# BW1098OAK_Power_Supply.net
KiCad netlist of a schematic drawn in Altium Designer
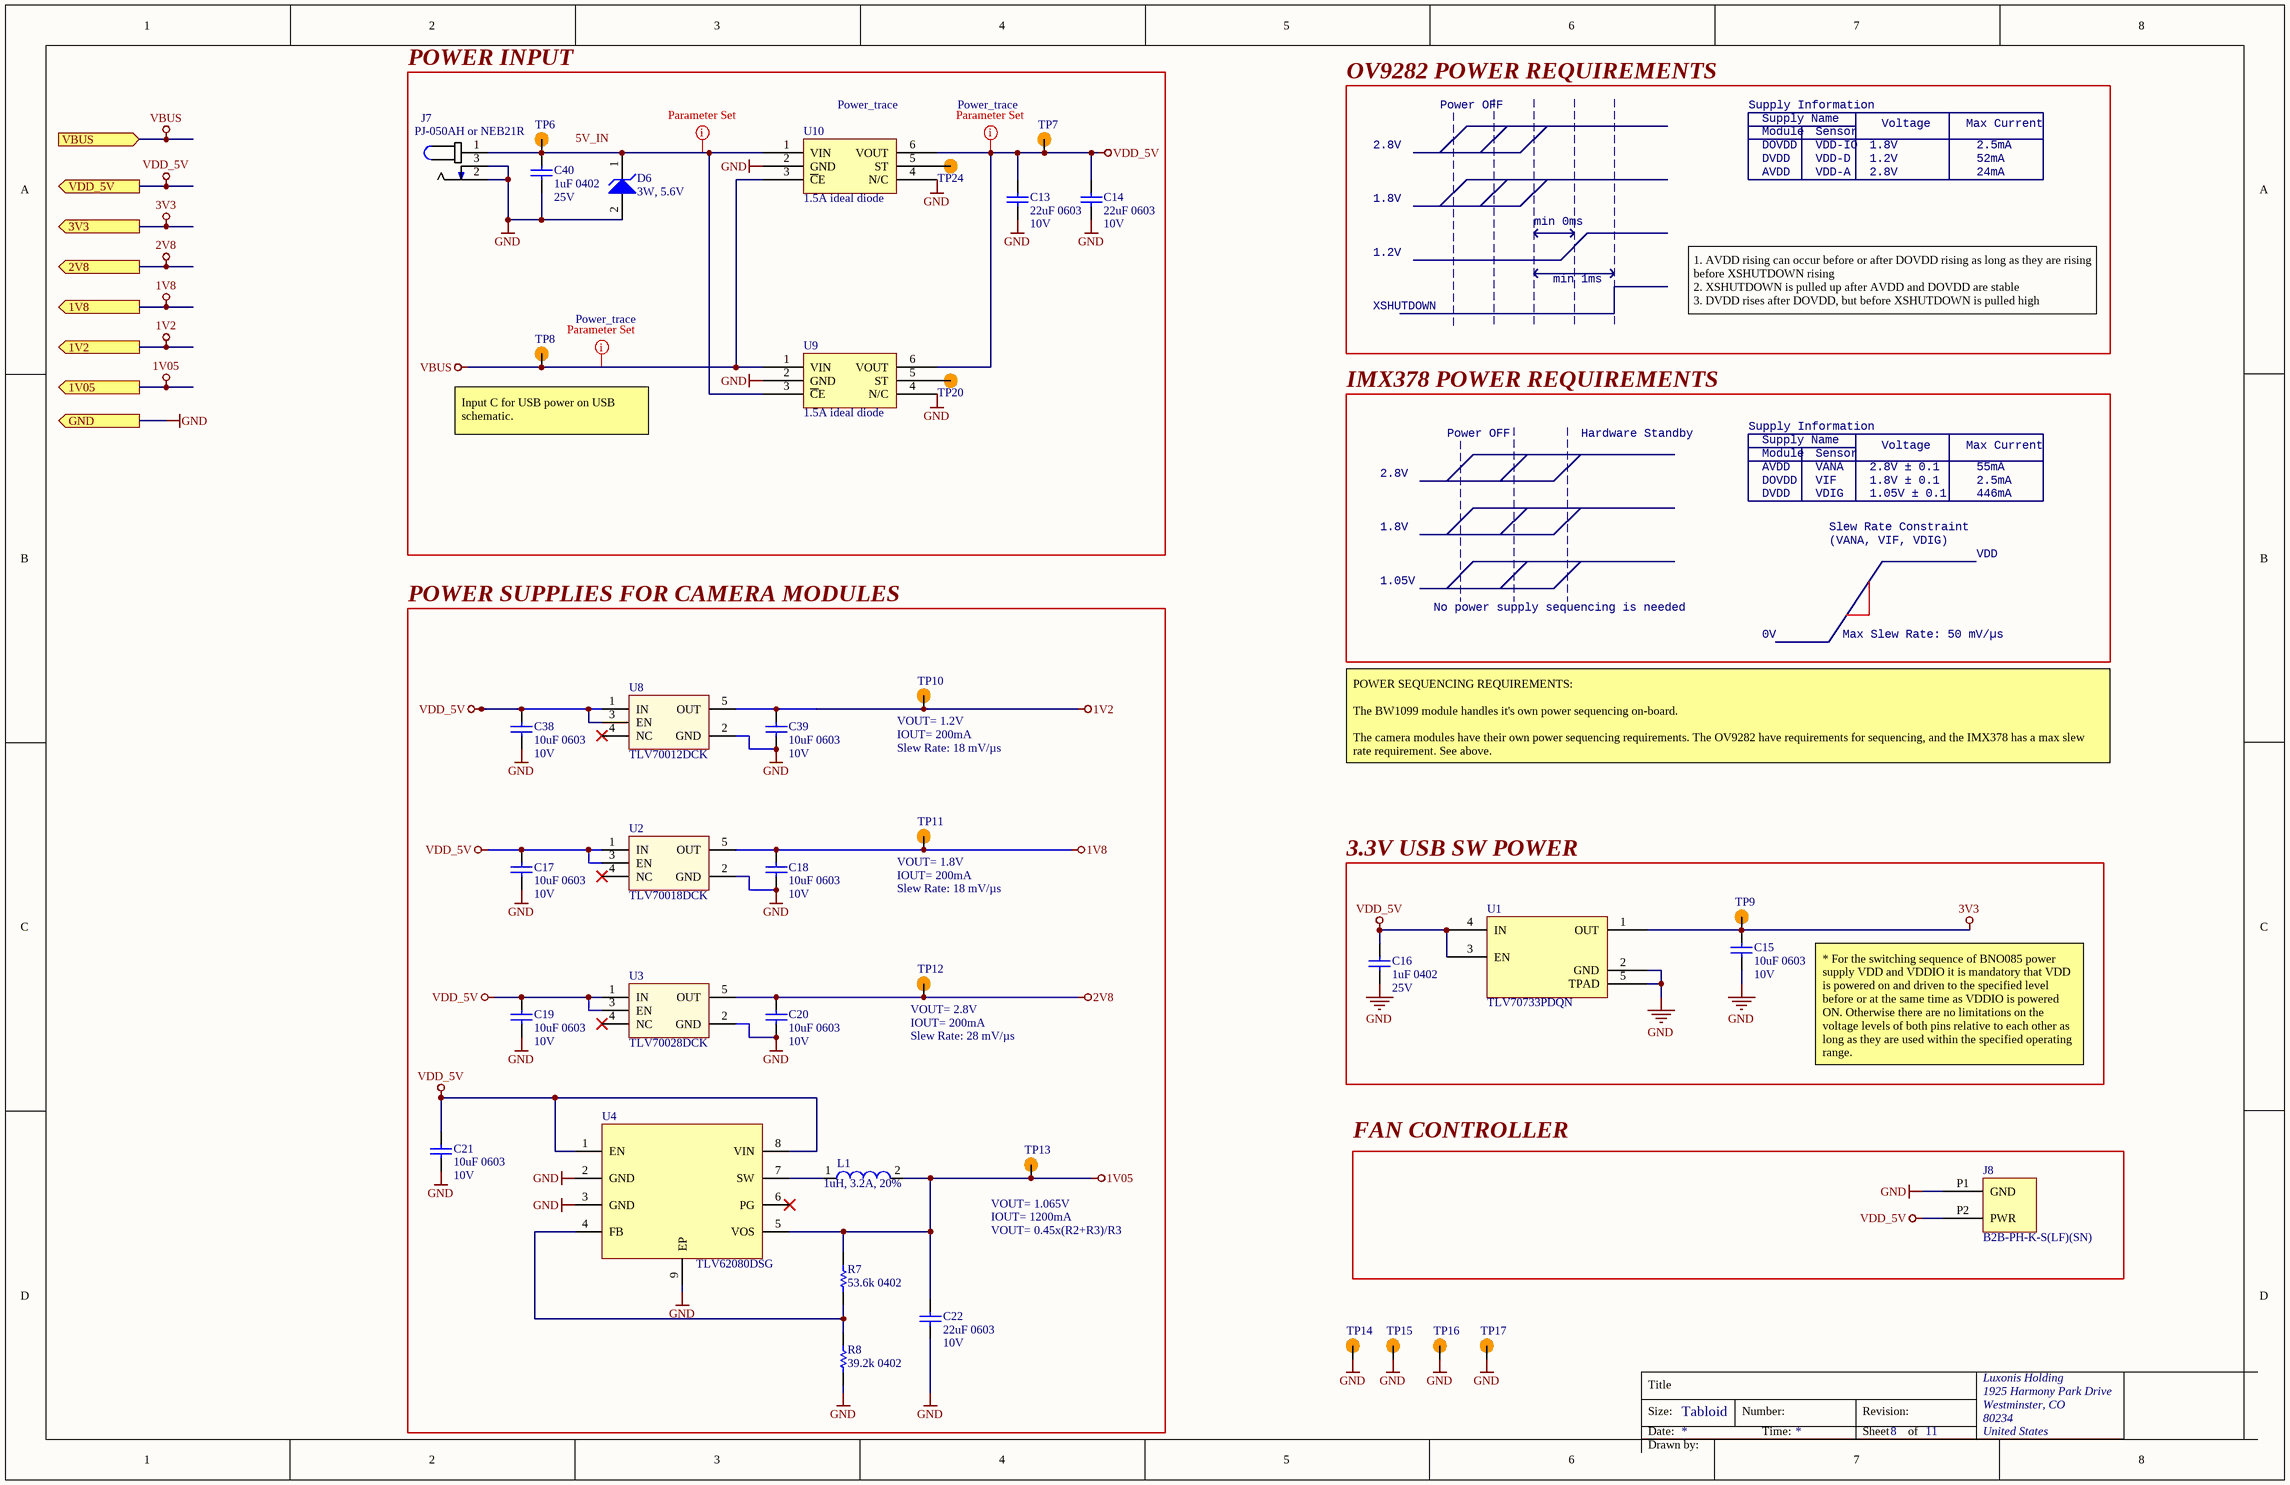
[diagram p0: BW1098OAK_Power_Supply.SchDoc]

(export (version "E")
  (design (tool "Eeschema 10.0.6"))
  (components
    (comp (ref "C13")
      (value "22uF 0603")
      (footprint "CAP_Altium_Vault_Generic:CAPC0603(1608)100_L")
      (description "CAP CER 22UF 10V X5R 0603 20%")
      (fields (field (name "TOLERANCE") "20%") (field (name "VOLTAGE RATING") "10V"))
      (libsource (lib "LuxonisMaster") (part "GRM188R61A226ME15D"))
    )
    (comp (ref "C14")
      (value "22uF 0603")
      (footprint "CAP_Altium_Vault_Generic:CAPC0603(1608)100_L")
      (description "CAP CER 22UF 10V X5R 0603 20%")
      (fields (field (name "TOLERANCE") "20%") (field (name "VOLTAGE RATING") "10V"))
      (libsource (lib "LuxonisMaster") (part "GRM188R61A226ME15D"))
    )
    (comp (ref "C15")
      (value "10uF 0603")
      (footprint "CAP_Altium_Vault_Generic:CAPC0603(1608)100_L")
      (description "CAP CER 10UF 10V X5R 0603 20%")
      (fields (field (name "TOLERANCE") "20%") (field (name "VOLTAGE RATING") "10V"))
      (libsource (lib "LuxonisMaster") (part "GRM188R61A106ME69D"))
    )
    (comp (ref "C16")
      (value "1uF 0402")
      (footprint "CAP_Altium_Vault_Generic:CAPC0402(1005)70_L")
      (description "CAP CER 1UF 25V X5R 0402 10%")
      (fields
        (field (name "TOLERANCE") "10%")
        (field (name "VOLTAGE") "25V")
        (field (name "VOLTAGE RATING") "25V")
      )
      (libsource (lib "LuxonisMaster") (part "GRM155R61E105KA12D"))
    )
    (comp (ref "C17")
      (value "10uF 0603")
      (footprint "CAP_Altium_Vault_Generic:CAPC0603(1608)100_L")
      (description "CAP CER 10UF 10V X5R 0603 20%")
      (fields (field (name "TOLERANCE") "20%") (field (name "VOLTAGE RATING") "10V"))
      (libsource (lib "LuxonisMaster") (part "GRM188R61A106ME69D"))
    )
    (comp (ref "C18")
      (value "10uF 0603")
      (footprint "CAP_Altium_Vault_Generic:CAPC0603(1608)100_L")
      (description "CAP CER 10UF 10V X5R 0603 20%")
      (fields (field (name "TOLERANCE") "20%") (field (name "VOLTAGE RATING") "10V"))
      (libsource (lib "LuxonisMaster") (part "GRM188R61A106ME69D"))
    )
    (comp (ref "C19")
      (value "10uF 0603")
      (footprint "CAP_Altium_Vault_Generic:CAPC0603(1608)100_L")
      (description "CAP CER 10UF 10V X5R 0603 20%")
      (fields (field (name "TOLERANCE") "20%") (field (name "VOLTAGE RATING") "10V"))
      (libsource (lib "LuxonisMaster") (part "GRM188R61A106ME69D"))
    )
    (comp (ref "C20")
      (value "10uF 0603")
      (footprint "CAP_Altium_Vault_Generic:CAPC0603(1608)100_L")
      (description "CAP CER 10UF 10V X5R 0603 20%")
      (fields (field (name "TOLERANCE") "20%") (field (name "VOLTAGE RATING") "10V"))
      (libsource (lib "LuxonisMaster") (part "GRM188R61A106ME69D"))
    )
    (comp (ref "C21")
      (value "10uF 0603")
      (footprint "CAP_Altium_Vault_Generic:CAPC0603(1608)100_L")
      (description "CAP CER 10UF 10V X5R 0603 20%")
      (fields (field (name "TOLERANCE") "20%") (field (name "VOLTAGE RATING") "10V"))
      (libsource (lib "LuxonisMaster") (part "GRM188R61A106ME69D"))
    )
    (comp (ref "C22")
      (value "22uF 0603")
      (footprint "CAP_Altium_Vault_Generic:CAPC0603(1608)100_L")
      (description "CAP CER 22UF 10V X5R 0603 20%")
      (fields (field (name "TOLERANCE") "20%") (field (name "VOLTAGE RATING") "10V"))
      (libsource (lib "LuxonisMaster") (part "GRM188R61A226ME15D"))
    )
    (comp (ref "C38")
      (value "10uF 0603")
      (footprint "CAP_Altium_Vault_Generic:CAPC0603(1608)100_L")
      (description "CAP CER 10UF 10V X5R 0603 20%")
      (fields (field (name "TOLERANCE") "20%") (field (name "VOLTAGE RATING") "10V"))
      (libsource (lib "LuxonisMaster") (part "GRM188R61A106ME69D"))
    )
    (comp (ref "C39")
      (value "10uF 0603")
      (footprint "CAP_Altium_Vault_Generic:CAPC0603(1608)100_L")
      (description "CAP CER 10UF 10V X5R 0603 20%")
      (fields (field (name "TOLERANCE") "20%") (field (name "VOLTAGE RATING") "10V"))
      (libsource (lib "LuxonisMaster") (part "GRM188R61A106ME69D"))
    )
    (comp (ref "C40")
      (value "1uF 0402")
      (footprint "CAP_Altium_Vault_Generic:CAPC0402(1005)70_L")
      (description "CAP CER 1UF 25V X5R 0402 10%")
      (fields
        (field (name "TOLERANCE") "10%")
        (field (name "VOLTAGE") "25V")
        (field (name "VOLTAGE RATING") "25V")
      )
      (libsource (lib "LuxonisMaster") (part "GRM155R61E105KA12D"))
    )
    (comp (ref "D6")
      (value "3W, 5.6V")
      (footprint "BW1098OBC_R3M1E3:1SMB5919BT3G")
      (description "DIODE ZENER 5.6V 3W SMB")
      (fields (field (name "TOLERANCE") "5%"))
      (libsource (lib "BW1098OAK_R0M0E0") (part "1SMB5919BT3G"))
    )
    (comp (ref "J7")
      (value "PJ-050AH or NEB21R")
      (footprint "LuxonisMaster:PJ-050AH/NEB21R_COMBO")
      (description "CONN POWER PIN 2 POS RA PTH Barrel jack 2.1mm x 5.5mm combo footprint")
      (libsource (lib "LuxonisMaster") (part "PJ-050AH/NEB21R_COMBO"))
    )
    (comp (ref "J8")
      (value "B2B-PH-K-S(LF)(SN)")
      (footprint "LuxonisMaster:B2B-PH-K-S(LF)(SN)")
      (description "CONN HEADER VERT 2POS 2MM")
      (libsource (lib "LuxonisMaster") (part "B2B-PH-K-S(LF)(SN)"))
    )
    (comp (ref "L1")
      (value "1uH, 3.2A, 20%")
      (footprint "LuxonisMaster:DFE252012P-1R0M=P2")
      (description "FIXED IND 1UH 3.2A 42 MOHM SMD")
      (fields
        (field (name "MANUFACTURER") "Murata")
        (field (name "MANUFACTURER PART NUMBER") "DFE252012P-1R0M=P2")
      )
      (libsource (lib "LuxonisMaster") (part "DFE252012P-1R0M=P2"))
    )
    (comp (ref "R7")
      (value "53.6k 0402")
      (footprint "RES_Altium_Vault_Generic:RESC0402(1005)_L")
      (description "RES SMD 53.6K OHM 1% 1/16W 0402")
      (fields (field (name "TOLERANCE") "1%"))
      (libsource (lib "LuxonisMaster") (part "CRCW040253K6FKED"))
    )
    (comp (ref "R8")
      (value "39.2k 0402")
      (footprint "RES_Altium_Vault_Generic:RESC0402(1005)_L")
      (description "RES SMD 39.2K OHM 1% 1/16W 0402")
      (fields (field (name "TOLERANCE") "1%"))
      (libsource (lib "LuxonisMaster") (part "CRCW040239K2FKED"))
    )
    (comp (ref "TP6")
      (value "TP100_200_NS")
      (footprint "LuxonisMaster:TP100_200_NS")
      (libsource (lib "LuxonisMaster") (part "TEST_POINT"))
    )
    (comp (ref "TP7")
      (value "TP100_200_NS")
      (footprint "LuxonisMaster:TP100_200_NS")
      (libsource (lib "LuxonisMaster") (part "TEST_POINT"))
    )
    (comp (ref "TP8")
      (value "TP100_200_NS")
      (footprint "LuxonisMaster:TP100_200_NS")
      (libsource (lib "LuxonisMaster") (part "TEST_POINT"))
    )
    (comp (ref "TP9")
      (value "TP100_200_NS")
      (footprint "LuxonisMaster:TP100_200_NS")
      (libsource (lib "LuxonisMaster") (part "TEST_POINT"))
    )
    (comp (ref "TP10")
      (value "TP100_200_NS")
      (footprint "LuxonisMaster:TP100_200_NS")
      (libsource (lib "LuxonisMaster") (part "TEST_POINT"))
    )
    (comp (ref "TP11")
      (value "TP100_200_NS")
      (footprint "LuxonisMaster:TP100_200_NS")
      (libsource (lib "LuxonisMaster") (part "TEST_POINT"))
    )
    (comp (ref "TP12")
      (value "TP100_200_NS")
      (footprint "LuxonisMaster:TP100_200_NS")
      (libsource (lib "LuxonisMaster") (part "TEST_POINT"))
    )
    (comp (ref "TP13")
      (value "TP100_200_NS")
      (footprint "LuxonisMaster:TP100_200_NS")
      (libsource (lib "LuxonisMaster") (part "TEST_POINT"))
    )
    (comp (ref "TP14")
      (value "TP100_200_NS")
      (footprint "LuxonisMaster:TP100_200_NS")
      (libsource (lib "LuxonisMaster") (part "TEST_POINT"))
    )
    (comp (ref "TP15")
      (value "TP100_200_NS")
      (footprint "LuxonisMaster:TP100_200_NS")
      (libsource (lib "LuxonisMaster") (part "TEST_POINT"))
    )
    (comp (ref "TP16")
      (value "TP100_200_NS")
      (footprint "LuxonisMaster:TP100_200_NS")
      (libsource (lib "LuxonisMaster") (part "TEST_POINT"))
    )
    (comp (ref "TP17")
      (value "TP100_200_NS")
      (footprint "LuxonisMaster:TP100_200_NS")
      (libsource (lib "LuxonisMaster") (part "TEST_POINT"))
    )
    (comp (ref "TP20")
      (value "TP100_200_NS")
      (footprint "LuxonisMaster:TP100_200_NS")
      (libsource (lib "LuxonisMaster") (part "TEST_POINT"))
    )
    (comp (ref "TP24")
      (value "TP100_200_NS")
      (footprint "LuxonisMaster:TP100_200_NS")
      (libsource (lib "LuxonisMaster") (part "TEST_POINT"))
    )
    (comp (ref "U1")
      (value "TLV70733PDQN")
      (footprint "LuxonisMaster:TLV70733PDQN")
      (description "IC REG LINEAR 3.3V 200MA 4X2SON Linear Voltage Regulator IC  1 Output  200mA 4-X2SON (1x1)")
      (libsource (lib "LuxonisMaster") (part "TLV70733PDQN"))
    )
    (comp (ref "U2")
      (value "TLV70018DCK")
      (footprint "LuxonisMaster:TLV70018DCK")
      (description "IC REG LINEAR 1.8V 200MA SC70-5 Linear Voltage Regulator IC  1 Output  200mA SC-70-5")
      (libsource (lib "LuxonisMaster") (part "TLV70018DCK"))
    )
    (comp (ref "U3")
      (value "TLV70028DCK")
      (footprint "LuxonisMaster:TLV70028DCK")
      (description "IC REG LINEAR 2.8V 200MA SC70-5 Linear Voltage Regulator IC  1 Output  200mA SC-70-5")
      (libsource (lib "LuxonisMaster") (part "TLV70028DCK"))
    )
    (comp (ref "U4")
      (value "TLV62080DSG")
      (footprint "LuxonisMaster:TLV62080DSG")
      (description "IC REG BUCK ADJ 1.2A SYNC 8WSON")
      (libsource (lib "LuxonisMaster") (part "TLV62080DSG"))
    )
    (comp (ref "U8")
      (value "TLV70012DCK")
      (footprint "LuxonisMaster:TLV70012DCK")
      (description "IC REG LINEAR 1.2V 200MA SC70-5")
      (libsource (lib "LuxonisMaster") (part "TLV70012DCK"))
    )
    (comp (ref "U9")
      (value "1.5A ideal diode")
      (footprint "LuxonisMaster:LM66100DCKR")
      (description "IC OR CTRLR IDEAL DIODE SC70-6")
      (libsource (lib "LuxonisMaster") (part "LM66100DCKR"))
    )
    (comp (ref "U10")
      (value "1.5A ideal diode")
      (footprint "LuxonisMaster:LM66100DCKR")
      (description "IC OR CTRLR IDEAL DIODE SC70-6")
      (libsource (lib "LuxonisMaster") (part "LM66100DCKR"))
    )
  )
  (nets
    (net (code "2") (name "1V2") (class "Default")
      (node (ref "C39") (pin "2") (pinfunction "2_2") (pintype "passive"))
      (node (ref "TP10") (pin "1") (pintype "passive"))
      (node (ref "U8") (pin "5") (pinfunction "OUT_5") (pintype "passive"))
    )
    (net (code "3") (name "1V05") (class "Default")
      (node (ref "C22") (pin "2") (pinfunction "2_2") (pintype "passive"))
      (node (ref "L1") (pin "2") (pinfunction "2_2") (pintype "passive"))
      (node (ref "R7") (pin "2") (pinfunction "2_2") (pintype "passive"))
      (node (ref "TP13") (pin "1") (pintype "passive"))
      (node (ref "U4") (pin "5") (pinfunction "VOS_5") (pintype "passive"))
    )
    (net (code "4") (name "1V8") (class "Default")
      (node (ref "C18") (pin "2") (pinfunction "2_2") (pintype "passive"))
      (node (ref "TP11") (pin "1") (pintype "passive"))
      (node (ref "U2") (pin "5") (pinfunction "OUT_5") (pintype "passive"))
    )
    (net (code "5") (name "2V8") (class "Default")
      (node (ref "C20") (pin "2") (pinfunction "2_2") (pintype "passive"))
      (node (ref "TP12") (pin "1") (pintype "passive"))
      (node (ref "U3") (pin "5") (pinfunction "OUT_5") (pintype "passive"))
    )
    (net (code "6") (name "3V3") (class "Default")
      (node (ref "C15") (pin "2") (pinfunction "2_2") (pintype "passive"))
      (node (ref "TP9") (pin "1") (pintype "passive"))
      (node (ref "U1") (pin "1") (pinfunction "OUT_1") (pintype "power_in"))
    )
    (net (code "7") (name "GND") (class "Default")
      (node (ref "C13") (pin "1") (pinfunction "1_1") (pintype "passive"))
      (node (ref "C14") (pin "1") (pinfunction "1_1") (pintype "passive"))
      (node (ref "C15") (pin "1") (pinfunction "1_1") (pintype "passive"))
      (node (ref "C16") (pin "1") (pinfunction "1_1") (pintype "passive"))
      (node (ref "C17") (pin "1") (pinfunction "1_1") (pintype "passive"))
      (node (ref "C18") (pin "1") (pinfunction "1_1") (pintype "passive"))
      (node (ref "C19") (pin "1") (pinfunction "1_1") (pintype "passive"))
      (node (ref "C20") (pin "1") (pinfunction "1_1") (pintype "passive"))
      (node (ref "C21") (pin "1") (pinfunction "1_1") (pintype "passive"))
      (node (ref "C22") (pin "1") (pinfunction "1_1") (pintype "passive"))
      (node (ref "C38") (pin "1") (pinfunction "1_1") (pintype "passive"))
      (node (ref "C39") (pin "1") (pinfunction "1_1") (pintype "passive"))
      (node (ref "C40") (pin "1") (pinfunction "1_1") (pintype "passive"))
      (node (ref "D6") (pin "2") (pinfunction "A_2") (pintype "passive"))
      (node (ref "J7") (pin "2") (pinfunction "2_2") (pintype "passive"))
      (node (ref "J7") (pin "3") (pinfunction "3_3") (pintype "passive"))
      (node (ref "J8") (pin "P1") (pinfunction "GND_P1") (pintype "passive"))
      (node (ref "R8") (pin "1") (pinfunction "1_1") (pintype "passive"))
      (node (ref "TP14") (pin "1") (pintype "passive"))
      (node (ref "TP15") (pin "1") (pintype "passive"))
      (node (ref "TP16") (pin "1") (pintype "passive"))
      (node (ref "TP17") (pin "1") (pintype "passive"))
      (node (ref "U1") (pin "2") (pinfunction "GND_2") (pintype "power_in"))
      (node (ref "U1") (pin "5") (pinfunction "TPAD_5") (pintype "passive"))
      (node (ref "U10") (pin "2") (pinfunction "GND_2") (pintype "passive"))
      (node (ref "U10") (pin "4") (pinfunction "N/C_4") (pintype "passive"))
      (node (ref "U2") (pin "2") (pinfunction "GND_2") (pintype "passive"))
      (node (ref "U3") (pin "2") (pinfunction "GND_2") (pintype "passive"))
      (node (ref "U4") (pin "2") (pinfunction "GND_2") (pintype "passive"))
      (node (ref "U4") (pin "3") (pinfunction "GND_3") (pintype "passive"))
      (node (ref "U4") (pin "9") (pinfunction "EP_9") (pintype "passive"))
      (node (ref "U8") (pin "2") (pinfunction "GND_2") (pintype "passive"))
      (node (ref "U9") (pin "2") (pinfunction "GND_2") (pintype "passive"))
      (node (ref "U9") (pin "4") (pinfunction "N/C_4") (pintype "passive"))
    )
    (net (code "8") (name "Net-(D6-K)") (class "Default")
      (node (ref "C40") (pin "2") (pinfunction "2_2") (pintype "passive"))
      (node (ref "D6") (pin "1") (pinfunction "K_1") (pintype "passive"))
      (node (ref "J7") (pin "1") (pinfunction "1_1") (pintype "passive"))
      (node (ref "TP6") (pin "1") (pintype "passive"))
      (node (ref "U10") (pin "1") (pinfunction "VIN_1") (pintype "passive"))
      (node (ref "U9") (pin "3") (pinfunction "~{C}E_3") (pintype "passive"))
    )
    (net (code "9") (name "Net-(U4-FB)") (class "Default")
      (node (ref "R7") (pin "1") (pinfunction "1_1") (pintype "passive"))
      (node (ref "R8") (pin "2") (pinfunction "2_2") (pintype "passive"))
      (node (ref "U4") (pin "4") (pinfunction "FB_4") (pintype "passive"))
    )
    (net (code "10") (name "Net-(U4-SW)") (class "Default")
      (node (ref "L1") (pin "1") (pinfunction "1_1") (pintype "passive"))
      (node (ref "U4") (pin "7") (pinfunction "SW_7") (pintype "passive"))
    )
    (net (code "11") (name "Net-(U9-ST)") (class "Default")
      (node (ref "TP20") (pin "1") (pintype "passive"))
      (node (ref "U9") (pin "5") (pinfunction "ST_5") (pintype "passive"))
    )
    (net (code "12") (name "Net-(U10-ST)") (class "Default")
      (node (ref "TP24") (pin "1") (pintype "passive"))
      (node (ref "U10") (pin "5") (pinfunction "ST_5") (pintype "passive"))
    )
    (net (code "13") (name "VBUS") (class "Default")
      (node (ref "TP8") (pin "1") (pintype "passive"))
      (node (ref "U10") (pin "3") (pinfunction "~{C}E_3") (pintype "passive"))
      (node (ref "U9") (pin "1") (pinfunction "VIN_1") (pintype "passive"))
    )
    (net (code "14") (name "VDD_5V") (class "Default")
      (node (ref "C13") (pin "2") (pinfunction "2_2") (pintype "passive"))
      (node (ref "C14") (pin "2") (pinfunction "2_2") (pintype "passive"))
      (node (ref "C16") (pin "2") (pinfunction "2_2") (pintype "passive"))
      (node (ref "C17") (pin "2") (pinfunction "2_2") (pintype "passive"))
      (node (ref "C19") (pin "2") (pinfunction "2_2") (pintype "passive"))
      (node (ref "C21") (pin "2") (pinfunction "2_2") (pintype "passive"))
      (node (ref "C38") (pin "2") (pinfunction "2_2") (pintype "passive"))
      (node (ref "J8") (pin "P2") (pinfunction "PWR_P2") (pintype "passive"))
      (node (ref "TP7") (pin "1") (pintype "passive"))
      (node (ref "U1") (pin "3") (pinfunction "EN_3") (pintype "power_in"))
      (node (ref "U1") (pin "4") (pinfunction "IN_4") (pintype "power_in"))
      (node (ref "U10") (pin "6") (pinfunction "VOUT_6") (pintype "passive"))
      (node (ref "U2") (pin "1") (pinfunction "IN_1") (pintype "passive"))
      (node (ref "U2") (pin "3") (pinfunction "EN_3") (pintype "passive"))
      (node (ref "U3") (pin "1") (pinfunction "IN_1") (pintype "passive"))
      (node (ref "U3") (pin "3") (pinfunction "EN_3") (pintype "passive"))
      (node (ref "U4") (pin "1") (pinfunction "EN_1") (pintype "passive"))
      (node (ref "U4") (pin "8") (pinfunction "VIN_8") (pintype "passive"))
      (node (ref "U8") (pin "1") (pinfunction "IN_1") (pintype "passive"))
      (node (ref "U8") (pin "3") (pinfunction "EN_3") (pintype "passive"))
      (node (ref "U9") (pin "6") (pinfunction "VOUT_6") (pintype "passive"))
    )
    (net (code "15") (name "unconnected-(U2-NC-Pad4)") (class "Default")
      (node (ref "U2") (pin "4") (pinfunction "NC_4") (pintype "passive+no_connect"))
    )
    (net (code "16") (name "unconnected-(U3-NC-Pad4)") (class "Default")
      (node (ref "U3") (pin "4") (pinfunction "NC_4") (pintype "passive+no_connect"))
    )
    (net (code "17") (name "unconnected-(U4-PG-Pad6)") (class "Default")
      (node (ref "U4") (pin "6") (pinfunction "PG_6") (pintype "passive+no_connect"))
    )
    (net (code "18") (name "unconnected-(U8-NC-Pad4)") (class "Default")
      (node (ref "U8") (pin "4") (pinfunction "NC_4") (pintype "passive+no_connect"))
    )
  )
)
